# Qwiic_Distance_Sensor_-_VL53L1X.net
KiCad netlist of a schematic drawn in EAGLE
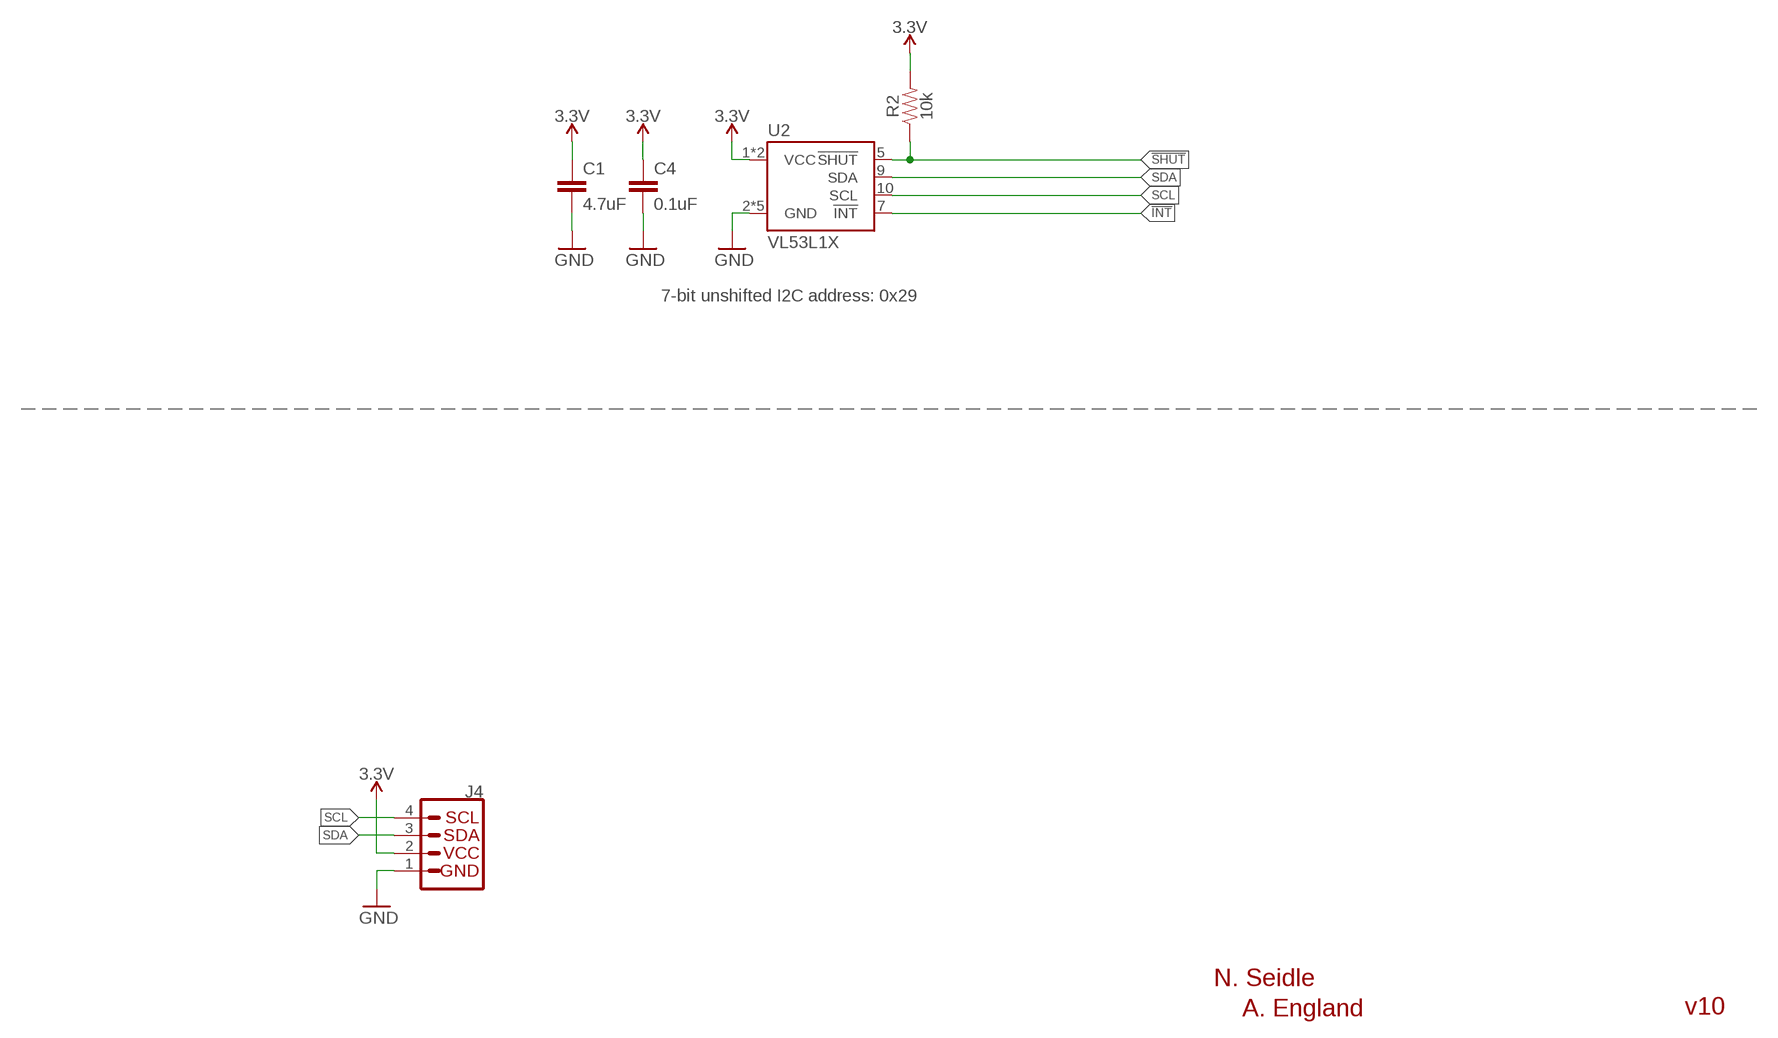
[diagram p0: schematic, sheet 1]

(export (version "E")
  (design (tool "Eeschema 10.0.6"))
  (components
    (comp (ref "C1")
      (value "4.7uF")
      (footprint "eagle-import:0603")
      (libsource (lib "eagle-import") (part "4.7UF0603"))
    )
    (comp (ref "C4")
      (value "0.1uF")
      (footprint "eagle-import:0603")
      (libsource (lib "eagle-import") (part "0.1UF-0603-25V-(+80/-20%)"))
    )
    (comp (ref "J4")
      (value "QWIIC_CONNECTORJS-1MM")
      (footprint "eagle-import:1X04_1MM_RA")
      (libsource (lib "eagle-import") (part "QWIIC_CONNECTORJS-1MM"))
    )
    (comp (ref "R2")
      (value "10k")
      (footprint "eagle-import:0603")
      (libsource (lib "eagle-import") (part "10KOHM-0603-1/10W-1%"))
    )
    (comp (ref "U2")
      (value "VL53L1X")
      (footprint "eagle-import:VL53L1X")
      (libsource (lib "eagle-import") (part "VL53L1XSMD"))
    )
  )
  (nets
    (net (code "1") (name "/~{INT}") (class "Default")
      (node (ref "U2") (pin "7") (pinfunction "~{INT}_7") (pintype "bidirectional"))
    )
    (net (code "2") (name "/~{SHUT}") (class "Default")
      (node (ref "R2") (pin "1") (pinfunction "1_1") (pintype "passive"))
      (node (ref "U2") (pin "5") (pinfunction "~{SHUT}_5") (pintype "bidirectional"))
    )
    (net (code "3") (name "3.3V") (class "Default")
      (node (ref "C1") (pin "1") (pinfunction "1_1") (pintype "passive"))
      (node (ref "C4") (pin "1") (pinfunction "1_1") (pintype "passive"))
      (node (ref "J4") (pin "2") (pinfunction "2_2") (pintype "power_in"))
      (node (ref "R2") (pin "2") (pinfunction "2_2") (pintype "passive"))
      (node (ref "U2") (pin "1") (pinfunction "VCC_1") (pintype "bidirectional"))
      (node (ref "U2") (pin "11") (pinfunction "VCC_11") (pintype "bidirectional"))
    )
    (net (code "4") (name "GND") (class "Default")
      (node (ref "C1") (pin "2") (pinfunction "2_2") (pintype "passive"))
      (node (ref "C4") (pin "2") (pinfunction "2_2") (pintype "passive"))
      (node (ref "J4") (pin "1") (pinfunction "1_1") (pintype "power_in"))
      (node (ref "U2") (pin "12") (pinfunction "GND_12") (pintype "bidirectional"))
      (node (ref "U2") (pin "2") (pinfunction "GND_2") (pintype "bidirectional"))
      (node (ref "U2") (pin "3") (pinfunction "GND_3") (pintype "bidirectional"))
      (node (ref "U2") (pin "4") (pinfunction "GND_4") (pintype "bidirectional"))
      (node (ref "U2") (pin "6") (pinfunction "GND_6") (pintype "bidirectional"))
    )
    (net (code "5") (name "SCL") (class "Default")
      (node (ref "J4") (pin "4") (pinfunction "4_4") (pintype "passive"))
      (node (ref "U2") (pin "10") (pinfunction "SCL_10") (pintype "bidirectional"))
    )
    (net (code "6") (name "SDA") (class "Default")
      (node (ref "J4") (pin "3") (pinfunction "3_3") (pintype "passive"))
      (node (ref "U2") (pin "9") (pinfunction "SDA_9") (pintype "bidirectional"))
    )
  )
)
